# V2_0.net
KiCad netlist of a schematic drawn in Altium Designer
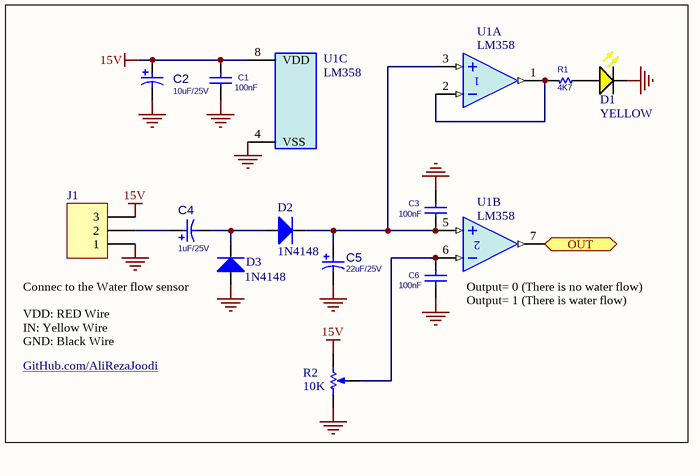
[diagram p0: V2.0.SchDoc]

(export (version "E")
  (design (tool "Eeschema 10.0.6"))
  (components
    (comp (ref "C1")
      (value "100nF")
      (footprint "C_THD_CER_(P2.54-D3.5-T1.5)")
      (description "Capacitor, Ceramic Multilayer")
      (libsource (lib "Passive") (part "Capacitor_Ceramic"))
    )
    (comp (ref "C2")
      (value "10uF/25V")
      (footprint "C_THD_EL_(P2.54-D6-H11)")
      (description "Capacitor, Electrolytic")
      (libsource (lib "Passive") (part "Capacitor_Electrolytic"))
    )
    (comp (ref "C3")
      (value "100nF")
      (footprint "C_THD_CER_(P2.54-D3.5-T1.5)")
      (description "Capacitor, Ceramic Multilayer")
      (libsource (lib "Passive") (part "Capacitor_Ceramic"))
    )
    (comp (ref "C4")
      (value "1uF/25V")
      (footprint "C_THD_EL_(P2.54-D6-H11)")
      (description "Capacitor, Electrolytic")
      (libsource (lib "Passive") (part "Capacitor_Electrolytic"))
    )
    (comp (ref "C5")
      (value "22uF/25V")
      (footprint "C_THD_EL_(P2.54-D6-H11)")
      (description "Capacitor, Electrolytic")
      (libsource (lib "Passive") (part "Capacitor_Electrolytic"))
    )
    (comp (ref "C6")
      (value "100nF")
      (footprint "C_THD_CER_(P2.54-D3.5-T1.5)")
      (description "Capacitor, Ceramic Multilayer")
      (libsource (lib "Passive") (part "Capacitor_Ceramic"))
    )
    (comp (ref "D1")
      (value "YELLOW")
      (footprint "LED_THD_5MM_YELLOW")
      (description "LED, Yellow")
      (fields (field (name "MANUFACTURER") "Generic Components") (field (name "PUBLISHER") "Altium Limited"))
      (libsource (lib "Display") (part "LED_YELLOW"))
    )
    (comp (ref "D2")
      (value "1N4148")
      (footprint "D_THD_AXIAL0.3_DO-35")
      (description "Default Diode")
      (fields (field (name "MANUFACTURER") "Generic Components") (field (name "PUBLISHER") "Altium Limited"))
      (libsource (lib "Miscellaneous Devices") (part "Diode"))
    )
    (comp (ref "D3")
      (value "1N4148")
      (footprint "D_THD_AXIAL0.3_DO-35")
      (description "Default Diode")
      (fields (field (name "MANUFACTURER") "Generic Components") (field (name "PUBLISHER") "Altium Limited"))
      (libsource (lib "Miscellaneous Devices") (part "Diode"))
    )
    (comp (ref "J1")
      (value "3PIN")
      (footprint "Connector_Phoenix_3PIN_MSTB")
      (description "Header, 3-Pin")
      (fields (field (name "MANUFACTURER") "Generic Components") (field (name "PUBLISHER") "Altium Limited"))
      (libsource (lib "Miscellaneous Connectors") (part "Header 3"))
    )
    (comp (ref "R1")
      (value "4K7")
      (footprint "R_THD_AXIAL0.4(1/4W)")
      (description "Resistor,")
      (libsource (lib "Passive") (part "Resistor"))
    )
    (comp (ref "R2")
      (value "10K")
      (footprint "POT_THD_3296W")
      (description "Potentiometer")
      (libsource (lib "Passive") (part "Resistor_Pot"))
    )
    (comp (ref "U1")
      (value "LM358")
      (footprint "751-02_L")
      (description "Dual Low-Power Operational Amplifier")
      (fields (field (name "PUBLISHER") "Altium Limited"))
      (libsource (lib "Op-Amp") (part "LM358"))
    )
  )
  (nets
    (net (code "1") (name "/OUT") (class "Default")
      (node (ref "U1") (pin "7") (pinfunction "OUT_7") (pintype "output"))
    )
    (net (code "2") (name "15V") (class "Default")
      (node (ref "C1") (pin "1") (pinfunction "1_1") (pintype "passive"))
      (node (ref "C2") (pin "1") (pinfunction "1_1") (pintype "passive"))
      (node (ref "J1") (pin "3") (pinfunction "3_3") (pintype "passive"))
      (node (ref "R2") (pin "3") (pinfunction "BOT_3") (pintype "passive"))
      (node (ref "U1") (pin "8") (pinfunction "VDD_8") (pintype "passive"))
    )
    (net (code "3") (name "GND") (class "Default")
      (node (ref "C1") (pin "2") (pinfunction "2_2") (pintype "passive"))
      (node (ref "C2") (pin "2") (pinfunction "2_2") (pintype "passive"))
      (node (ref "C3") (pin "2") (pinfunction "2_2") (pintype "passive"))
      (node (ref "C5") (pin "2") (pinfunction "2_2") (pintype "passive"))
      (node (ref "C6") (pin "2") (pinfunction "2_2") (pintype "passive"))
      (node (ref "D1") (pin "2") (pinfunction "K_2") (pintype "passive"))
      (node (ref "D3") (pin "1") (pinfunction "A_1") (pintype "passive"))
      (node (ref "J1") (pin "1") (pinfunction "1_1") (pintype "passive"))
      (node (ref "R2") (pin "1") (pinfunction "TOP_1") (pintype "passive"))
      (node (ref "U1") (pin "4") (pinfunction "VSS_4") (pintype "power_in"))
    )
    (net (code "4") (name "Net-(C4-Pad1)") (class "Default")
      (node (ref "C4") (pin "1") (pinfunction "1_1") (pintype "passive"))
      (node (ref "J1") (pin "2") (pinfunction "2_2") (pintype "passive"))
    )
    (net (code "5") (name "Net-(D1-A)") (class "Default")
      (node (ref "D1") (pin "1") (pinfunction "A_1") (pintype "passive"))
      (node (ref "R1") (pin "2") (pinfunction "2_2") (pintype "passive"))
    )
    (net (code "6") (name "Net-(D2-A)") (class "Default")
      (node (ref "C4") (pin "2") (pinfunction "2_2") (pintype "passive"))
      (node (ref "D2") (pin "1") (pinfunction "A_1") (pintype "passive"))
      (node (ref "D3") (pin "2") (pinfunction "K_2") (pintype "passive"))
    )
    (net (code "7") (name "Net-(D2-K)") (class "Default")
      (node (ref "C3") (pin "1") (pinfunction "1_1") (pintype "passive"))
      (node (ref "C5") (pin "1") (pinfunction "1_1") (pintype "passive"))
      (node (ref "D2") (pin "2") (pinfunction "K_2") (pintype "passive"))
      (node (ref "U1") (pin "3") (pinfunction "IN+_3") (pintype "input"))
      (node (ref "U1") (pin "5") (pinfunction "IN+_5") (pintype "input"))
    )
    (net (code "8") (name "Net-(R2-TAP)") (class "Default")
      (node (ref "C6") (pin "1") (pinfunction "1_1") (pintype "passive"))
      (node (ref "R2") (pin "2") (pinfunction "TAP_2") (pintype "passive"))
      (node (ref "U1") (pin "6") (pinfunction "IN-_6") (pintype "input"))
    )
    (net (code "9") (name "Net-(U1A-IN-)") (class "Default")
      (node (ref "R1") (pin "1") (pinfunction "1_1") (pintype "passive"))
      (node (ref "U1") (pin "1") (pinfunction "OUT_1") (pintype "output"))
      (node (ref "U1") (pin "2") (pinfunction "IN-_2") (pintype "input"))
    )
  )
)
